# 02_Power.net
KiCad netlist of a schematic drawn in Altium Designer
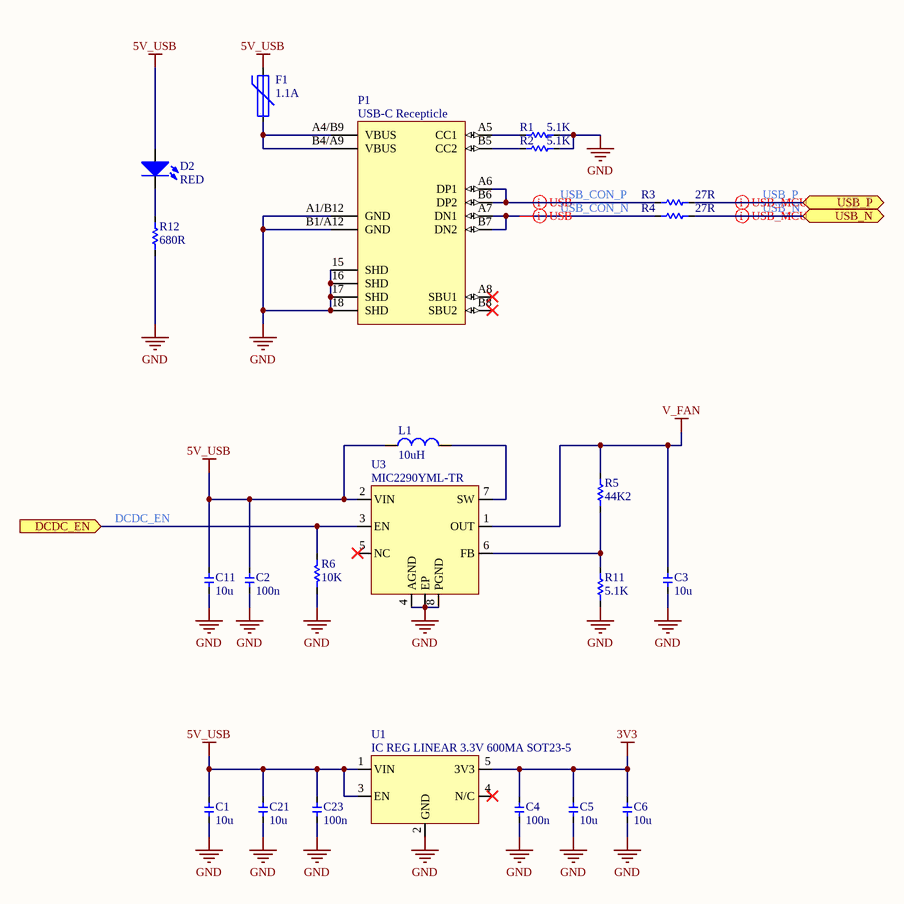
[diagram p0: 02_Power.SchDoc]

(export (version "E")
  (design (tool "Eeschema 10.0.6"))
  (components
    (comp (ref "C1")
      (value "10u")
      (footprint "Footprint_Misc:0402")
      (description "Capacitor")
      (fields
        (field (name "MANUFACTURER") "Murata Electronics")
        (field (name "MANUFACTURER PART NUMBER") "GRM155R61A106ME11D")
      )
      (libsource (lib "Schematic_Misc") (part "Cap"))
    )
    (comp (ref "C2")
      (value "100n")
      (footprint "Footprint_Misc:0402")
      (description "Capacitor")
      (fields
        (field (name "MANUFACTURER") "Samsung Electro-Mechanics")
        (field (name "MANUFACTURER PART NUMBER") "CL05B104KA5NNNC")
      )
      (libsource (lib "Schematic_Misc") (part "Cap"))
    )
    (comp (ref "C3")
      (value "10u")
      (footprint "Footprint_Misc:0805")
      (description "Capacitor")
      (fields
        (field (name "MANUFACTURER") "Samsung Electro-Mechanics")
        (field (name "MANUFACTURER PART NUMBER") "CL21B106KOQNNNE")
      )
      (libsource (lib "Schematic_Misc") (part "Cap"))
    )
    (comp (ref "C4")
      (value "100n")
      (footprint "Footprint_Misc:0402")
      (description "Capacitor")
      (fields
        (field (name "MANUFACTURER") "Samsung Electro-Mechanics")
        (field (name "MANUFACTURER PART NUMBER") "CL05B104KA5NNNC")
      )
      (libsource (lib "Schematic_Misc") (part "Cap"))
    )
    (comp (ref "C5")
      (value "10u")
      (footprint "Footprint_Misc:0603 - CAP")
      (description "Capacitor")
      (fields
        (field (name "MANUFACTURER") "Murata Electronics")
        (field (name "MANUFACTURER PART NUMBER") "GRM188Z71A106KA73D")
      )
      (libsource (lib "Schematic_Misc") (part "Cap"))
    )
    (comp (ref "C6")
      (value "10u")
      (footprint "Footprint_Misc:0603 - CAP")
      (description "Capacitor")
      (fields
        (field (name "MANUFACTURER") "Murata Electronics")
        (field (name "MANUFACTURER PART NUMBER") "GRM188Z71A106KA73D")
      )
      (libsource (lib "Schematic_Misc") (part "Cap"))
    )
    (comp (ref "C11")
      (value "10u")
      (footprint "Footprint_Misc:0402")
      (description "Capacitor")
      (fields
        (field (name "MANUFACTURER") "Murata Electronics")
        (field (name "MANUFACTURER PART NUMBER") "GRM155R61A106ME11D")
      )
      (libsource (lib "Schematic_Misc") (part "Cap"))
    )
    (comp (ref "C21")
      (value "10u")
      (footprint "Footprint_Misc:0603 - CAP")
      (description "Capacitor")
      (fields
        (field (name "MANUFACTURER") "Murata Electronics")
        (field (name "MANUFACTURER PART NUMBER") "GRM188Z71A106KA73D")
      )
      (libsource (lib "Schematic_Misc") (part "Cap"))
    )
    (comp (ref "C23")
      (value "100n")
      (footprint "Footprint_Misc:0402")
      (description "Capacitor")
      (fields
        (field (name "MANUFACTURER") "Samsung Electro-Mechanics")
        (field (name "MANUFACTURER PART NUMBER") "CL05B104KA5NNNC")
      )
      (libsource (lib "Schematic_Misc") (part "Cap"))
    )
    (comp (ref "D2")
      (value "RED")
      (footprint "Footprint_Misc:CD1608-0603")
      (description "5mA 26.05mcd 无色透明透镜 -30℃~+85℃ 631nm Red 130° 50mW 2V 0603 Light Emitting Diodes (LED) ROHS")
      (fields
        (field (name "MANUFACTURER") "Lite-On")
        (field (name "MANUFACTURER PART NUMBER") "LTST-C193KRKT-5A")
      )
      (libsource (lib "LCSC") (part "LED-0603-5mA-RED"))
    )
    (comp (ref "F1")
      (value "1.1A")
      (footprint "Footprint_Misc:FUSE_2114X12N")
      (description "6V 1.1A 40A 2.2A 0805 Resettable Fuses ROHS")
      (fields
        (field (name "MANUFACTURER") "BOURNS")
        (field (name "MANUFACTURER PART NUMBER") "MF-PSMF110X-2")
      )
      (libsource (lib "LCSC") (part "Fuse-PTC-0805-0.5A_6V"))
    )
    (comp (ref "L1")
      (value "10uH")
      (footprint "Footprint_Misc:INDC3218X20N")
      (description "10 µH Shielded Drum Core, Wirewound Inductor 850 mA 480mOhm Max 1008 (2520 Metric)")
      (fields
        (field (name "MANUFACTURER") "Pulse Electronics")
        (field (name "MANUFACTURER PART NUMBER") "BWMR00252012100M00")
      )
      (libsource (lib "LCSC") (part "L-2520-10uH 850mA 480mOhm"))
    )
    (comp (ref "P1")
      (value "USB-C Recepticle")
      (footprint "Footprint_Misc:GCT_USB4105-GF-A")
      (description "3A 1 Surface Mount 16P Female -25℃~+85℃ Type-C SMD USB Connectors ROHS")
      (fields
        (field (name "MANUFACTURER") "DEALON")
        (field (name "MANUFACTURER PART NUMBER") "USB-TYPE-C-019")
      )
      (libsource (lib "Schematic_Misc") (part "USB-C Recepticle -USB-TYPE-C-019"))
    )
    (comp (ref "R1")
      (value "5.1K")
      (footprint "Footprint_Misc:0402")
      (description "Resistor")
      (fields (field (name "DISTRIBUTOR PART NUMBER") "C105872") (field (name "MANUFACTURER") "YAGEO"))
      (libsource (lib "Schematic_Misc") (part "Res"))
    )
    (comp (ref "R2")
      (value "5.1K")
      (footprint "Footprint_Misc:0402")
      (description "Resistor")
      (fields (field (name "DISTRIBUTOR PART NUMBER") "C105872") (field (name "MANUFACTURER") "YAGEO"))
      (libsource (lib "Schematic_Misc") (part "Res"))
    )
    (comp (ref "R3")
      (value "27R")
      (footprint "Footprint_Misc:0402")
      (description "Resistor")
      (fields (field (name "MANUFACTURER") "YAGEO") (field (name "DISTRIBUTOR PART NUMBER") "C138021"))
      (libsource (lib "Schematic_Misc") (part "Res"))
    )
    (comp (ref "R4")
      (value "27R")
      (footprint "Footprint_Misc:0402")
      (description "Resistor")
      (fields (field (name "MANUFACTURER") "YAGEO") (field (name "DISTRIBUTOR PART NUMBER") "C138021"))
      (libsource (lib "Schematic_Misc") (part "Res"))
    )
    (comp (ref "R5")
      (value "44K2")
      (footprint "0402")
      (description "44.2 kOhms ±1% 0.1W, 1/10W Chip Resistor 0603 (1608 Metric) Moisture Resistant Thick Film")
      (fields
        (field (name "MANUFACTURER") "YAGEO")
        (field (name "MANUFACTURER PART NUMBER") "RC0402FR-0744K2L")
      )
      (libsource (lib "LCSC") (part "R-0603-44K2 1%"))
    )
    (comp (ref "R6")
      (value "10K")
      (footprint "Footprint_Misc:0402")
      (description "Resistor")
      (fields (field (name "DISTRIBUTOR PART NUMBER") "C60490") (field (name "MANUFACTURER") "YAGEO"))
      (libsource (lib "Schematic_Misc") (part "Res"))
    )
    (comp (ref "R11")
      (value "5.1K")
      (footprint "Footprint_Misc:0402")
      (description "Resistor")
      (fields (field (name "DISTRIBUTOR PART NUMBER") "C105872") (field (name "MANUFACTURER") "YAGEO"))
      (libsource (lib "Schematic_Misc") (part "Res"))
    )
    (comp (ref "R12")
      (value "680R")
      (footprint "Footprint_Misc:0402")
      (description "470Ω 100mW Thick Film Resistors ±0.5% ±100ppm/℃ 0603 Chip Resistor - Surface Mount ROHS")
      (fields
        (field (name "MANUFACTURER") "YAGEO")
        (field (name "MANUFACTURER PART NUMBER") "RC0402FR-10680RL")
      )
      (libsource (lib "LCSC") (part "R-0603-470R 1%"))
    )
    (comp (ref "U1")
      (value "IC REG LINEAR 3.3V 600MA SOT23-5")
      (footprint "Moji Footprintovi:SOT-23-5")
      (description "600mA null 3.3V positive 6V SOT-25 Linear Voltage Regulators (LDO) ROHS")
      (fields
        (field (name "DISTRIBUTOR PART NUMBER") "C526385")
        (field (name "MANUFACTURER") "Diodes Incorporated")
      )
      (libsource (lib "Schematic_Misc") (part "AP7366-33W5-7"))
    )
    (comp (ref "U3")
      (value "MIC2290YML-TR")
      (footprint "Footprint_Misc:SON50P200X85_HS-9N")
      (fields
        (field (name "DISTRIBUTOR PART NUMBER") "C144214")
        (field (name "MANUFACTURER") "Microchip Technology")
      )
      (libsource (lib "LCSC") (part "MIC2290YML-TR"))
    )
  )
  (nets
    (net (code "1") (name "/DCDC_EN") (class "Default")
      (node (ref "R6") (pin "2") (pinfunction "2_2") (pintype "passive"))
      (node (ref "U3") (pin "3") (pinfunction "EN_3") (pintype "passive"))
    )
    (net (code "2") (name "/USB_CON_N") (class "Default")
      (node (ref "P1") (pin "A7") (pinfunction "DN1_A7") (pintype "bidirectional"))
      (node (ref "P1") (pin "B7") (pinfunction "DN2_B7") (pintype "bidirectional"))
      (node (ref "R4") (pin "2") (pinfunction "2_2") (pintype "passive"))
    )
    (net (code "3") (name "/USB_CON_P") (class "Default")
      (node (ref "P1") (pin "A6") (pinfunction "DP1_A6") (pintype "bidirectional"))
      (node (ref "P1") (pin "B6") (pinfunction "DP2_B6") (pintype "bidirectional"))
      (node (ref "R3") (pin "2") (pinfunction "2_2") (pintype "passive"))
    )
    (net (code "4") (name "/USB_N") (class "Default")
      (node (ref "R4") (pin "1") (pinfunction "1_1") (pintype "passive"))
    )
    (net (code "5") (name "/USB_P") (class "Default")
      (node (ref "R3") (pin "1") (pinfunction "1_1") (pintype "passive"))
    )
    (net (code "6") (name "3V3") (class "Default")
      (node (ref "C4") (pin "2") (pinfunction "2_2") (pintype "passive"))
      (node (ref "C5") (pin "2") (pinfunction "2_2") (pintype "passive"))
      (node (ref "C6") (pin "2") (pinfunction "2_2") (pintype "passive"))
      (node (ref "U1") (pin "5") (pinfunction "3V3_5") (pintype "passive"))
    )
    (net (code "7") (name "5V_USB") (class "Default")
      (node (ref "C1") (pin "2") (pinfunction "2_2") (pintype "passive"))
      (node (ref "C11") (pin "2") (pinfunction "2_2") (pintype "passive"))
      (node (ref "C2") (pin "2") (pinfunction "2_2") (pintype "passive"))
      (node (ref "C21") (pin "2") (pinfunction "2_2") (pintype "passive"))
      (node (ref "C23") (pin "2") (pinfunction "2_2") (pintype "passive"))
      (node (ref "D2") (pin "A") (pinfunction "A_A") (pintype "passive"))
      (node (ref "F1") (pin "2") (pinfunction "2_2") (pintype "passive"))
      (node (ref "L1") (pin "1") (pinfunction "1_1") (pintype "passive"))
      (node (ref "U1") (pin "1") (pinfunction "VIN_1") (pintype "passive"))
      (node (ref "U1") (pin "3") (pinfunction "EN_3") (pintype "passive"))
      (node (ref "U3") (pin "2") (pinfunction "VIN_2") (pintype "passive"))
    )
    (net (code "8") (name "GND") (class "Default")
      (node (ref "C1") (pin "1") (pinfunction "1_1") (pintype "passive"))
      (node (ref "C11") (pin "1") (pinfunction "1_1") (pintype "passive"))
      (node (ref "C2") (pin "1") (pinfunction "1_1") (pintype "passive"))
      (node (ref "C21") (pin "1") (pinfunction "1_1") (pintype "passive"))
      (node (ref "C23") (pin "1") (pinfunction "1_1") (pintype "passive"))
      (node (ref "C3") (pin "1") (pinfunction "1_1") (pintype "passive"))
      (node (ref "C4") (pin "1") (pinfunction "1_1") (pintype "passive"))
      (node (ref "C5") (pin "1") (pinfunction "1_1") (pintype "passive"))
      (node (ref "C6") (pin "1") (pinfunction "1_1") (pintype "passive"))
      (node (ref "P1") (pin "15") (pinfunction "SHD_15") (pintype "power_in"))
      (node (ref "P1") (pin "16") (pinfunction "SHD_16") (pintype "power_in"))
      (node (ref "P1") (pin "17") (pinfunction "SHD_17") (pintype "power_in"))
      (node (ref "P1") (pin "18") (pinfunction "SHD_18") (pintype "power_in"))
      (node (ref "P1") (pin "A1/B12") (pinfunction "GND_A1/B12") (pintype "power_in"))
      (node (ref "P1") (pin "B1/A12") (pinfunction "GND_B1/A12") (pintype "power_in"))
      (node (ref "R1") (pin "2") (pinfunction "2_2") (pintype "passive"))
      (node (ref "R11") (pin "1") (pinfunction "1_1") (pintype "passive"))
      (node (ref "R12") (pin "1") (pinfunction "1_1") (pintype "passive"))
      (node (ref "R2") (pin "2") (pinfunction "2_2") (pintype "passive"))
      (node (ref "R6") (pin "1") (pinfunction "1_1") (pintype "passive"))
      (node (ref "U1") (pin "2") (pinfunction "GND_2") (pintype "passive"))
      (node (ref "U3") (pin "4") (pinfunction "AGND_4") (pintype "passive"))
      (node (ref "U3") (pin "8") (pinfunction "PGND_8") (pintype "passive"))
      (node (ref "U3") (pin "EP") (pinfunction "EP_EP") (pintype "passive"))
    )
    (net (code "9") (name "Net-(D2-PadK)") (class "Default")
      (node (ref "D2") (pin "K") (pinfunction "K_K") (pintype "passive"))
      (node (ref "R12") (pin "2") (pinfunction "2_2") (pintype "passive"))
    )
    (net (code "10") (name "Net-(F1-Pad1)") (class "Default")
      (node (ref "F1") (pin "1") (pinfunction "1_1") (pintype "passive"))
      (node (ref "P1") (pin "A4/B9") (pinfunction "VBUS_A4/B9") (pintype "power_in"))
      (node (ref "P1") (pin "B4/A9") (pinfunction "VBUS_B4/A9") (pintype "power_in"))
    )
    (net (code "11") (name "Net-(P1-CC1)") (class "Default")
      (node (ref "P1") (pin "A5") (pinfunction "CC1_A5") (pintype "bidirectional"))
      (node (ref "R1") (pin "1") (pinfunction "1_1") (pintype "passive"))
    )
    (net (code "12") (name "Net-(P1-CC2)") (class "Default")
      (node (ref "P1") (pin "B5") (pinfunction "CC2_B5") (pintype "bidirectional"))
      (node (ref "R2") (pin "1") (pinfunction "1_1") (pintype "passive"))
    )
    (net (code "13") (name "Net-(U3-FB)") (class "Default")
      (node (ref "R11") (pin "2") (pinfunction "2_2") (pintype "passive"))
      (node (ref "R5") (pin "1") (pinfunction "1_1") (pintype "passive"))
      (node (ref "U3") (pin "6") (pinfunction "FB_6") (pintype "passive"))
    )
    (net (code "14") (name "Net-(U3-SW)") (class "Default")
      (node (ref "L1") (pin "2") (pinfunction "2_2") (pintype "passive"))
      (node (ref "U3") (pin "7") (pinfunction "SW_7") (pintype "passive"))
    )
    (net (code "15") (name "V_FAN") (class "Default")
      (node (ref "C3") (pin "2") (pinfunction "2_2") (pintype "passive"))
      (node (ref "R5") (pin "2") (pinfunction "2_2") (pintype "passive"))
      (node (ref "U3") (pin "1") (pinfunction "OUT_1") (pintype "passive"))
    )
    (net (code "16") (name "unconnected-(P1-SBU1-PadA8)") (class "Default")
      (node (ref "P1") (pin "A8") (pinfunction "SBU1_A8") (pintype "bidirectional+no_connect"))
    )
    (net (code "17") (name "unconnected-(P1-SBU2-PadB8)") (class "Default")
      (node (ref "P1") (pin "B8") (pinfunction "SBU2_B8") (pintype "bidirectional+no_connect"))
    )
    (net (code "18") (name "unconnected-(U1-N{slash}C-Pad4)") (class "Default")
      (node (ref "U1") (pin "4") (pinfunction "N/C_4") (pintype "passive+no_connect"))
    )
    (net (code "19") (name "unconnected-(U3-NC-Pad5)") (class "Default")
      (node (ref "U3") (pin "5") (pinfunction "NC_5") (pintype "passive+no_connect"))
    )
  )
)
